# WifiNode_Cpu0.net
KiCad netlist of a schematic drawn in Altium Designer
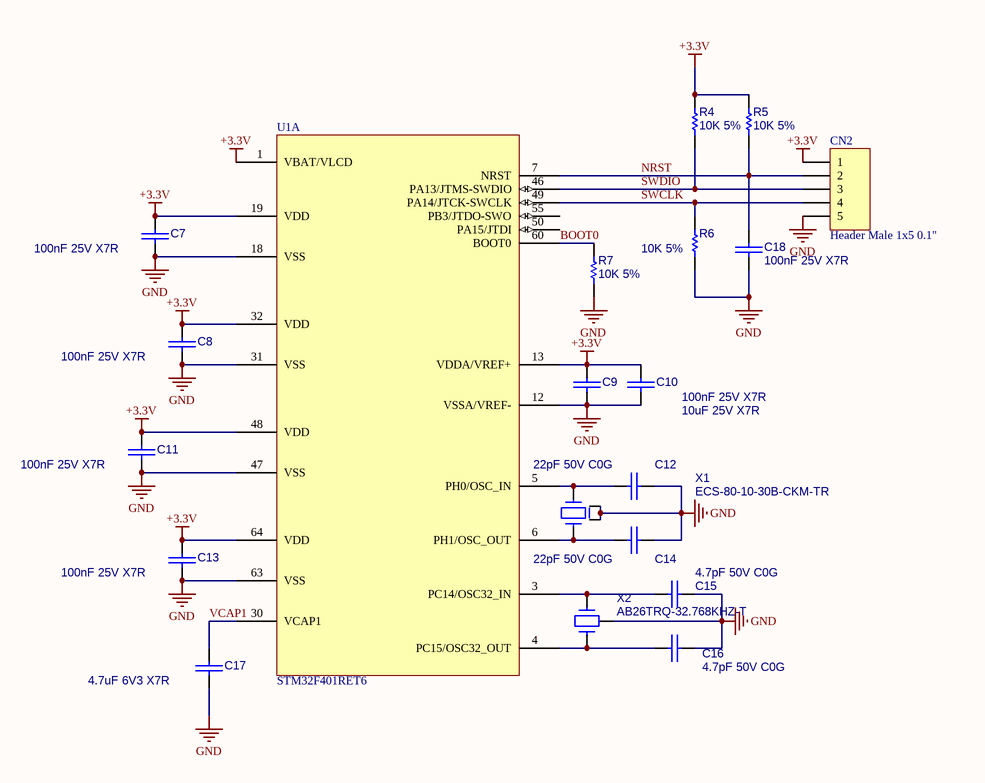
[diagram p0: WifiNode_Cpu0.SchDoc]

(export (version "E")
  (design (tool "Eeschema 10.0.6"))
  (components
    (comp (ref "C7")
      (value "100nF 25V X7R")
      (footprint "C_0805")
      (description "Non Polarized Capacitor")
      (libsource (lib "WifiNode") (part "CAP"))
    )
    (comp (ref "C8")
      (value "100nF 25V X7R")
      (footprint "C_0805")
      (description "Non Polarized Capacitor")
      (libsource (lib "WifiNode") (part "CAP"))
    )
    (comp (ref "C9")
      (value "100nF 25V X7R")
      (footprint "C_0805")
      (description "Non Polarized Capacitor")
      (libsource (lib "WifiNode") (part "CAP"))
    )
    (comp (ref "C10")
      (value "10uF 25V X7R")
      (footprint "C_0805")
      (description "Non Polarized Capacitor")
      (libsource (lib "WifiNode") (part "CAP"))
    )
    (comp (ref "C11")
      (value "100nF 25V X7R")
      (footprint "C_0805")
      (description "Non Polarized Capacitor")
      (libsource (lib "WifiNode") (part "CAP"))
    )
    (comp (ref "C12")
      (value "22pF 50V C0G")
      (footprint "C_0805")
      (description "Non Polarized Capacitor")
      (libsource (lib "WifiNode") (part "CAP"))
    )
    (comp (ref "C13")
      (value "100nF 25V X7R")
      (footprint "C_0805")
      (description "Non Polarized Capacitor")
      (libsource (lib "WifiNode") (part "CAP"))
    )
    (comp (ref "C14")
      (value "22pF 50V C0G")
      (footprint "C_0805")
      (description "Non Polarized Capacitor")
      (libsource (lib "WifiNode") (part "CAP"))
    )
    (comp (ref "C15")
      (value "4.7pF 50V C0G")
      (footprint "C_0805")
      (description "Non Polarized Capacitor")
      (libsource (lib "WifiNode") (part "CAP"))
    )
    (comp (ref "C16")
      (value "4.7pF 50V C0G")
      (footprint "C_0805")
      (description "Non Polarized Capacitor")
      (libsource (lib "WifiNode") (part "CAP"))
    )
    (comp (ref "C17")
      (value "4.7uF 6V3 X7R")
      (footprint "C_0805")
      (description "Non Polarized Capacitor")
      (libsource (lib "WifiNode") (part "CAP"))
    )
    (comp (ref "C18")
      (value "100nF 25V X7R")
      (footprint "C_0805")
      (description "Non Polarized Capacitor")
      (libsource (lib "WifiNode") (part "CAP"))
    )
    (comp (ref "CN2")
      (value "Header Male 1x5 0.1\"")
      (footprint "Header_M_1x5_0.1\"")
      (description "Connector Generic 5 Vias")
      (libsource (lib "WifiNode") (part "CONN_05P"))
    )
    (comp (ref "R4")
      (value "10K 5%")
      (footprint "R_0805")
      (description "Resistor")
      (libsource (lib "WifiNode") (part "Res1"))
    )
    (comp (ref "R5")
      (value "10K 5%")
      (footprint "R_0805")
      (description "Resistor")
      (libsource (lib "WifiNode") (part "Res1"))
    )
    (comp (ref "R6")
      (value "10K 5%")
      (footprint "R_0805")
      (description "Resistor")
      (libsource (lib "WifiNode") (part "Res1"))
    )
    (comp (ref "R7")
      (value "10K 5%")
      (footprint "R_0805")
      (description "Resistor")
      (libsource (lib "WifiNode") (part "Res1"))
    )
    (comp (ref "U1")
      (value "STM32F401RET6")
      (description "Microcontroller")
      (libsource (lib "WifiNode") (part "STM32F401RE"))
    )
    (comp (ref "X1")
      (value "ECS-80-10-30B-CKM-TR")
      (footprint "ABM3C")
      (description "Crystal 4 Vias + GND")
      (libsource (lib "WifiNode") (part "CRYSTAL_4P"))
    )
    (comp (ref "X2")
      (value "AB26TRQ-32.768KHZ-T")
      (footprint "AB26TQF")
      (description "Crystal 2 Vias + GND")
      (libsource (lib "WifiNode") (part "CRYSTAL 3P"))
    )
  )
  (nets
    (net (code "1") (name "+3.3V") (class "Default")
      (node (ref "C10") (pin "1") (pinfunction "1_1") (pintype "passive"))
      (node (ref "C11") (pin "1") (pinfunction "1_1") (pintype "passive"))
      (node (ref "C13") (pin "1") (pinfunction "1_1") (pintype "passive"))
      (node (ref "C7") (pin "1") (pinfunction "1_1") (pintype "passive"))
      (node (ref "C8") (pin "1") (pinfunction "1_1") (pintype "passive"))
      (node (ref "C9") (pin "1") (pinfunction "1_1") (pintype "passive"))
      (node (ref "CN2") (pin "1") (pinfunction "1_1") (pintype "passive"))
      (node (ref "R4") (pin "2") (pinfunction "2_2") (pintype "passive"))
      (node (ref "R5") (pin "2") (pinfunction "2_2") (pintype "passive"))
      (node (ref "U1") (pin "1") (pinfunction "VBAT/VLCD_1") (pintype "passive"))
      (node (ref "U1") (pin "13") (pinfunction "VDDA/VREF+_13") (pintype "passive"))
      (node (ref "U1") (pin "19") (pinfunction "VDD_19") (pintype "passive"))
      (node (ref "U1") (pin "32") (pinfunction "VDD_32") (pintype "passive"))
      (node (ref "U1") (pin "48") (pinfunction "VDD_48") (pintype "passive"))
      (node (ref "U1") (pin "64") (pinfunction "VDD_64") (pintype "passive"))
    )
    (net (code "2") (name "/BOOT0") (class "Default")
      (node (ref "R7") (pin "2") (pinfunction "2_2") (pintype "passive"))
      (node (ref "U1") (pin "60") (pinfunction "BOOT0_60") (pintype "passive"))
    )
    (net (code "3") (name "/NRST") (class "Default")
      (node (ref "C18") (pin "1") (pinfunction "1_1") (pintype "passive"))
      (node (ref "CN2") (pin "2") (pinfunction "2_2") (pintype "passive"))
      (node (ref "R5") (pin "1") (pinfunction "1_1") (pintype "passive"))
      (node (ref "U1") (pin "7") (pinfunction "NRST_7") (pintype "passive"))
    )
    (net (code "4") (name "/SWCLK") (class "Default")
      (node (ref "CN2") (pin "4") (pinfunction "4_4") (pintype "passive"))
      (node (ref "R6") (pin "2") (pinfunction "2_2") (pintype "passive"))
      (node (ref "U1") (pin "49") (pinfunction "PA14/JTCK-SWCLK_49") (pintype "bidirectional"))
    )
    (net (code "5") (name "/SWDIO") (class "Default")
      (node (ref "CN2") (pin "3") (pinfunction "3_3") (pintype "passive"))
      (node (ref "R4") (pin "1") (pinfunction "1_1") (pintype "passive"))
      (node (ref "U1") (pin "46") (pinfunction "PA13/JTMS-SWDIO_46") (pintype "bidirectional"))
    )
    (net (code "6") (name "/VCAP1") (class "Default")
      (node (ref "C17") (pin "1") (pinfunction "1_1") (pintype "passive"))
      (node (ref "U1") (pin "30") (pinfunction "VCAP1_30") (pintype "passive"))
    )
    (net (code "7") (name "GND") (class "Default")
      (node (ref "C10") (pin "2") (pinfunction "2_2") (pintype "passive"))
      (node (ref "C11") (pin "2") (pinfunction "2_2") (pintype "passive"))
      (node (ref "C12") (pin "2") (pinfunction "2_2") (pintype "passive"))
      (node (ref "C13") (pin "2") (pinfunction "2_2") (pintype "passive"))
      (node (ref "C14") (pin "2") (pinfunction "2_2") (pintype "passive"))
      (node (ref "C15") (pin "2") (pinfunction "2_2") (pintype "passive"))
      (node (ref "C16") (pin "2") (pinfunction "2_2") (pintype "passive"))
      (node (ref "C17") (pin "2") (pinfunction "2_2") (pintype "passive"))
      (node (ref "C18") (pin "2") (pinfunction "2_2") (pintype "passive"))
      (node (ref "C7") (pin "2") (pinfunction "2_2") (pintype "passive"))
      (node (ref "C8") (pin "2") (pinfunction "2_2") (pintype "passive"))
      (node (ref "C9") (pin "2") (pinfunction "2_2") (pintype "passive"))
      (node (ref "CN2") (pin "5") (pinfunction "5_5") (pintype "passive"))
      (node (ref "R6") (pin "1") (pinfunction "1_1") (pintype "passive"))
      (node (ref "R7") (pin "1") (pinfunction "1_1") (pintype "passive"))
      (node (ref "U1") (pin "12") (pinfunction "VSSA/VREF-_12") (pintype "passive"))
      (node (ref "U1") (pin "18") (pinfunction "VSS_18") (pintype "passive"))
      (node (ref "U1") (pin "31") (pinfunction "VSS_31") (pintype "passive"))
      (node (ref "U1") (pin "47") (pinfunction "VSS_47") (pintype "passive"))
      (node (ref "U1") (pin "63") (pinfunction "VSS_63") (pintype "passive"))
      (node (ref "X1") (pin "2") (pinfunction "2_2") (pintype "passive"))
      (node (ref "X1") (pin "4") (pinfunction "4_4") (pintype "passive"))
      (node (ref "X2") (pin "3") (pinfunction "3_3") (pintype "passive"))
    )
    (net (code "8") (name "Net-(U1A-PC14{slash}OSC32_IN)") (class "Default")
      (node (ref "C15") (pin "1") (pinfunction "1_1") (pintype "passive"))
      (node (ref "U1") (pin "3") (pinfunction "PC14/OSC32_IN_3") (pintype "passive"))
      (node (ref "X2") (pin "1") (pinfunction "1_1") (pintype "passive"))
    )
    (net (code "9") (name "Net-(U1A-PC15{slash}OSC32_OUT)") (class "Default")
      (node (ref "C16") (pin "1") (pinfunction "1_1") (pintype "passive"))
      (node (ref "U1") (pin "4") (pinfunction "PC15/OSC32_OUT_4") (pintype "passive"))
      (node (ref "X2") (pin "2") (pinfunction "2_2") (pintype "passive"))
    )
    (net (code "10") (name "Net-(U1A-PH0{slash}OSC_IN)") (class "Default")
      (node (ref "C12") (pin "1") (pinfunction "1_1") (pintype "passive"))
      (node (ref "U1") (pin "5") (pinfunction "PH0/OSC_IN_5") (pintype "passive"))
      (node (ref "X1") (pin "1") (pinfunction "1_1") (pintype "passive"))
    )
    (net (code "11") (name "Net-(U1A-PH1{slash}OSC_OUT)") (class "Default")
      (node (ref "C14") (pin "1") (pinfunction "1_1") (pintype "passive"))
      (node (ref "U1") (pin "6") (pinfunction "PH1/OSC_OUT_6") (pintype "passive"))
      (node (ref "X1") (pin "3") (pinfunction "3_3") (pintype "passive"))
    )
    (net (code "12") (name "unconnected-(U1A-PA15{slash}JTDI-Pad50)") (class "Default")
      (node (ref "U1") (pin "50") (pinfunction "PA15/JTDI_50") (pintype "bidirectional"))
    )
    (net (code "13") (name "unconnected-(U1A-PB3{slash}JTDO-SWO-Pad55)") (class "Default")
      (node (ref "U1") (pin "55") (pinfunction "PB3/JTDO-SWO_55") (pintype "bidirectional"))
    )
  )
)
